# 2_PIS____BHC-A-2030-02____V1_0_21.net
KiCad netlist of a schematic drawn in Altium Designer
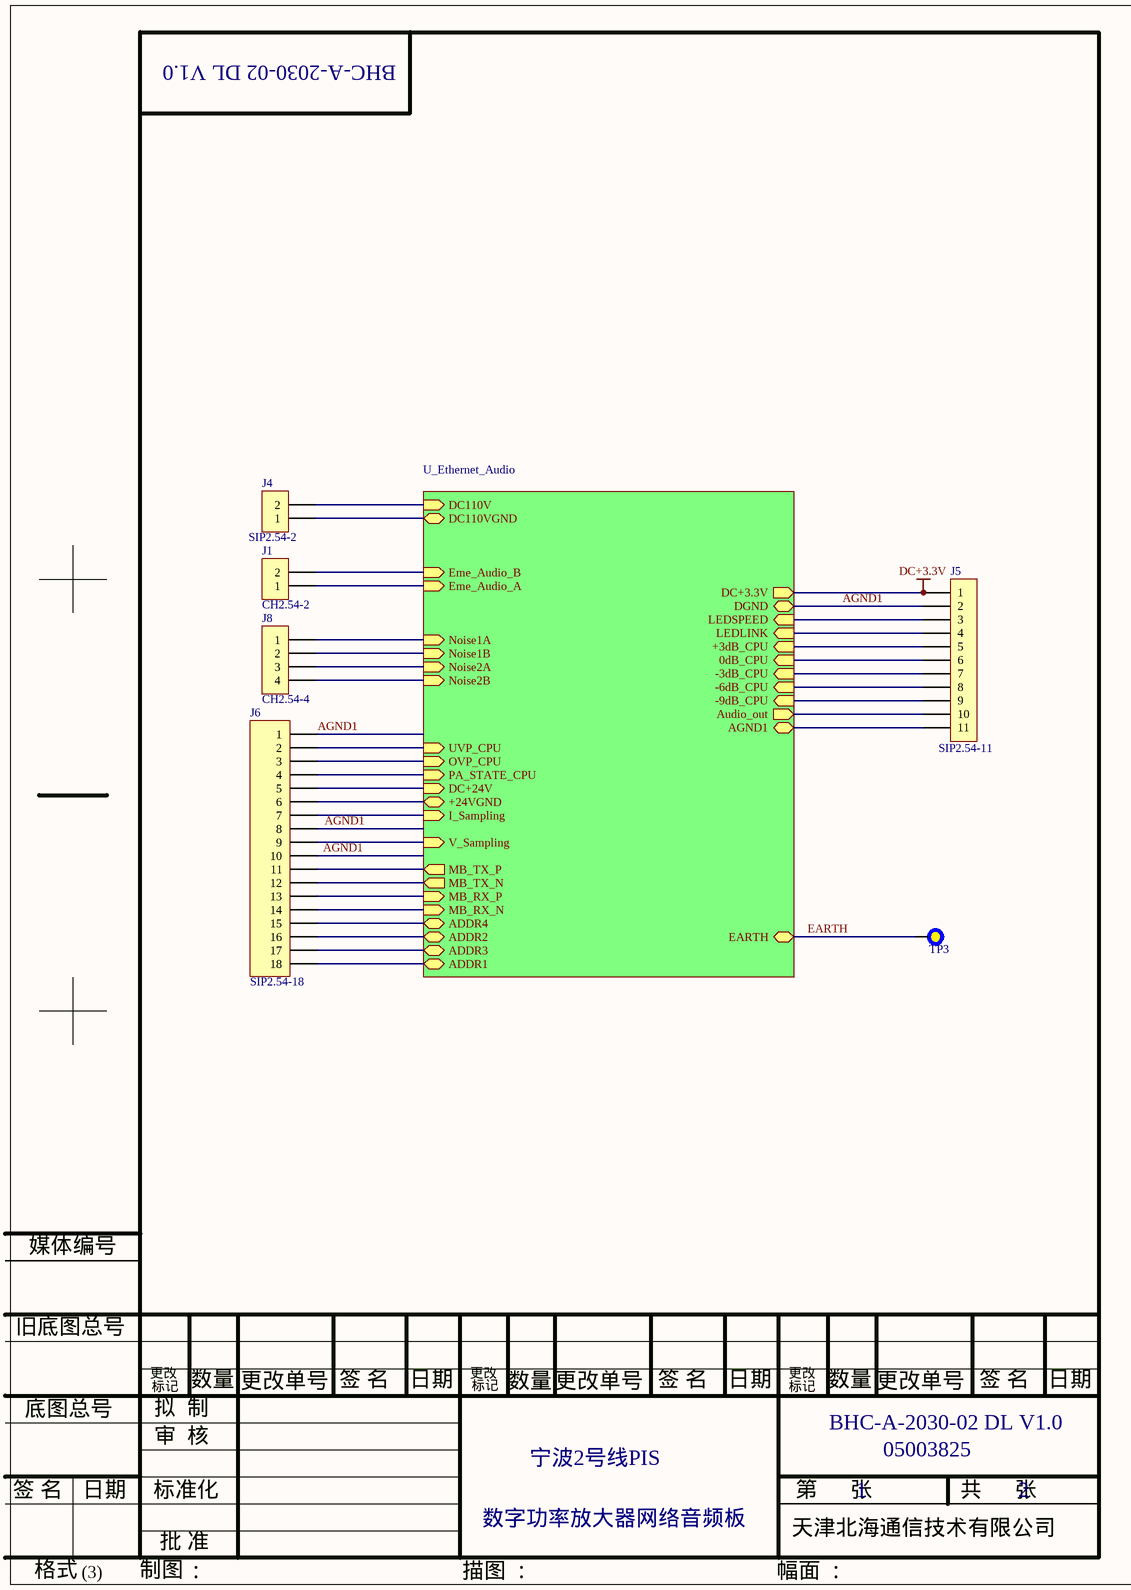
[diagram p0: 宁波2号线PIS_数字功率放大器_网络音频板(BHC-A-2030-02)_原理图_V1.0 (21).SchDoc]

(export (version "E")
  (design (tool "Eeschema 10.0.6"))
  (components
    (comp (ref "J1")
      (value "CH2.54-2")
      (footprint "CH2.54-2")
      (description "Connector")
      (fields (field (name "Comment") "CON2"))
      (libsource (lib "SCH") (part "CON2"))
    )
    (comp (ref "J4")
      (value "SIP2.54-2")
      (footprint "SIP2.54-2")
      (description "Connector")
      (fields (field (name "Comment") "CON2"))
      (libsource (lib "SCH") (part "CON2"))
    )
    (comp (ref "J5")
      (value "SIP2.54-11")
      (footprint "SIP2.54-11")
      (fields (field (name "Comment") "CON11"))
      (libsource (lib "SCH") (part "CON11"))
    )
    (comp (ref "J6")
      (value "SIP2.54-18")
      (footprint "SIP2.54-18")
      (description "Connector")
      (fields (field (name "Comment") "CON18"))
      (libsource (lib "SCH") (part "CON18"))
    )
    (comp (ref "J8")
      (value "CH2.54-4")
      (footprint "CH2.54-4")
      (fields (field (name "Comment") "CON4"))
      (libsource (lib "SCH") (part "CON4"))
    )
    (comp (ref "TP3") (value "TP") (footprint "TP") (libsource (lib "SCH") (part "TP")))
  )
  (nets
    (net (code "1") (name "/+3dB_CPU") (class "Default")
      (node (ref "J5") (pin "5") (pinfunction "5_5") (pintype "passive"))
    )
    (net (code "2") (name "/+24VGND") (class "Default")
      (node (ref "J6") (pin "6") (pinfunction "6_6") (pintype "passive"))
    )
    (net (code "3") (name "/-3dB_CPU") (class "Default")
      (node (ref "J5") (pin "7") (pinfunction "7_7") (pintype "passive"))
    )
    (net (code "4") (name "/-6dB_CPU") (class "Default")
      (node (ref "J5") (pin "8") (pinfunction "8_8") (pintype "passive"))
    )
    (net (code "5") (name "/-9dB_CPU") (class "Default")
      (node (ref "J5") (pin "9") (pinfunction "9_9") (pintype "passive"))
    )
    (net (code "6") (name "/0dB_CPU") (class "Default")
      (node (ref "J5") (pin "6") (pinfunction "6_6") (pintype "passive"))
    )
    (net (code "7") (name "/ADDR1") (class "Default")
      (node (ref "J6") (pin "18") (pinfunction "18_18") (pintype "passive"))
    )
    (net (code "8") (name "/ADDR2") (class "Default")
      (node (ref "J6") (pin "16") (pinfunction "16_16") (pintype "passive"))
    )
    (net (code "9") (name "/ADDR3") (class "Default")
      (node (ref "J6") (pin "17") (pinfunction "17_17") (pintype "passive"))
    )
    (net (code "10") (name "/ADDR4") (class "Default")
      (node (ref "J6") (pin "15") (pinfunction "15_15") (pintype "passive"))
    )
    (net (code "11") (name "/AGND1") (class "Default")
      (node (ref "J5") (pin "2") (pinfunction "2_2") (pintype "passive"))
      (node (ref "J6") (pin "1") (pinfunction "1_1") (pintype "passive"))
      (node (ref "J6") (pin "10") (pinfunction "10_10") (pintype "passive"))
      (node (ref "J6") (pin "8") (pinfunction "8_8") (pintype "passive"))
    )
    (net (code "12") (name "/AGND1_1") (class "Default")
      (node (ref "J5") (pin "11") (pinfunction "11_11") (pintype "passive"))
    )
    (net (code "13") (name "/Audio_out") (class "Default")
      (node (ref "J5") (pin "10") (pinfunction "10_10") (pintype "passive"))
    )
    (net (code "14") (name "/DC+24V") (class "Default")
      (node (ref "J6") (pin "5") (pinfunction "5_5") (pintype "passive"))
    )
    (net (code "15") (name "/DC110V") (class "Default")
      (node (ref "J4") (pin "2") (pinfunction "2_2") (pintype "passive"))
    )
    (net (code "16") (name "/DC110VGND") (class "Default")
      (node (ref "J4") (pin "1") (pinfunction "1_1") (pintype "passive"))
    )
    (net (code "17") (name "/EARTH") (class "Default")
      (node (ref "TP3") (pin "1") (pinfunction "1_1") (pintype "passive"))
    )
    (net (code "18") (name "/Eme_Audio_A") (class "Default")
      (node (ref "J1") (pin "1") (pinfunction "1_1") (pintype "passive"))
    )
    (net (code "19") (name "/Eme_Audio_B") (class "Default")
      (node (ref "J1") (pin "2") (pinfunction "2_2") (pintype "passive"))
    )
    (net (code "20") (name "/I_Sampling") (class "Default")
      (node (ref "J6") (pin "7") (pinfunction "7_7") (pintype "passive"))
    )
    (net (code "21") (name "/LEDLINK") (class "Default")
      (node (ref "J5") (pin "4") (pinfunction "4_4") (pintype "passive"))
    )
    (net (code "22") (name "/LEDSPEED") (class "Default")
      (node (ref "J5") (pin "3") (pinfunction "3_3") (pintype "passive"))
    )
    (net (code "23") (name "/MB_RX_N") (class "Default")
      (node (ref "J6") (pin "14") (pinfunction "14_14") (pintype "passive"))
    )
    (net (code "24") (name "/MB_RX_P") (class "Default")
      (node (ref "J6") (pin "13") (pinfunction "13_13") (pintype "passive"))
    )
    (net (code "25") (name "/MB_TX_N") (class "Default")
      (node (ref "J6") (pin "12") (pinfunction "12_12") (pintype "passive"))
    )
    (net (code "26") (name "/MB_TX_P") (class "Default")
      (node (ref "J6") (pin "11") (pinfunction "11_11") (pintype "passive"))
    )
    (net (code "27") (name "/Noise1A") (class "Default")
      (node (ref "J8") (pin "1") (pinfunction "1_1") (pintype "passive"))
    )
    (net (code "28") (name "/Noise1B") (class "Default")
      (node (ref "J8") (pin "2") (pinfunction "2_2") (pintype "passive"))
    )
    (net (code "29") (name "/Noise2A") (class "Default")
      (node (ref "J8") (pin "3") (pinfunction "3_3") (pintype "passive"))
    )
    (net (code "30") (name "/Noise2B") (class "Default")
      (node (ref "J8") (pin "4") (pinfunction "4_4") (pintype "passive"))
    )
    (net (code "31") (name "/OVP_CPU") (class "Default")
      (node (ref "J6") (pin "3") (pinfunction "3_3") (pintype "passive"))
    )
    (net (code "32") (name "/PA_STATE_CPU") (class "Default")
      (node (ref "J6") (pin "4") (pinfunction "4_4") (pintype "passive"))
    )
    (net (code "33") (name "/UVP_CPU") (class "Default")
      (node (ref "J6") (pin "2") (pinfunction "2_2") (pintype "passive"))
    )
    (net (code "34") (name "/V_Sampling") (class "Default")
      (node (ref "J6") (pin "9") (pinfunction "9_9") (pintype "passive"))
    )
    (net (code "35") (name "DC+3.3V") (class "Default")
      (node (ref "J5") (pin "1") (pinfunction "1_1") (pintype "passive"))
    )
  )
)
